# NOR_FLASH.net
KiCad netlist of a schematic drawn in Altium Designer
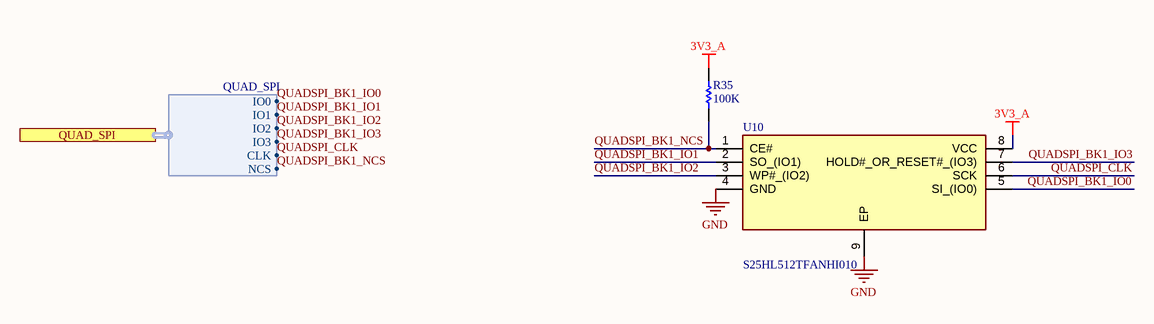
[diagram p0: NOR_FLASH.SchDoc]

(export (version "E")
  (design (tool "Eeschema 10.0.6"))
  (components
    (comp (ref "R35")
      (value "100K")
      (footprint "RESC1608X55X30ML20T10")
      (fields (field (name "PART NUMBER") "RK73B1JTTD104J") (field (name "MANUFACTURER") "KOA Speer"))
      (libsource (lib "Altium Content Vault") (part "RES"))
    )
    (comp (ref "U10")
      (value "S25HL512TFANHI010")
      (footprint "SamacSys:SON127P800X600X80-9N-D")
      (description "Integrated Circuit")
      (fields (field (name "MOUSER PART NUMBER") "727-S25HL512TFANHI01"))
      (libsource (lib "*") (part "S25HL512TFANHI010"))
    )
  )
  (nets
    (net (code "2") (name "/QUADSPI_BK1_IO0") (class "Default")
      (node (ref "U10") (pin "5") (pinfunction "SI_(IO0)_5") (pintype "passive"))
    )
    (net (code "3") (name "/QUADSPI_BK1_IO1") (class "Default")
      (node (ref "U10") (pin "2") (pinfunction "SO_(IO1)_2") (pintype "passive"))
    )
    (net (code "4") (name "/QUADSPI_BK1_IO2") (class "Default")
      (node (ref "U10") (pin "3") (pinfunction "WP#_(IO2)_3") (pintype "passive"))
    )
    (net (code "5") (name "/QUADSPI_BK1_IO3") (class "Default")
      (node (ref "U10") (pin "7") (pinfunction "HOLD#_OR_RESET#_(IO3)_7") (pintype "passive"))
    )
    (net (code "6") (name "/QUADSPI_BK1_NCS") (class "Default")
      (node (ref "R35") (pin "1") (pinfunction "1_1") (pintype "passive"))
      (node (ref "U10") (pin "1") (pinfunction "CE#_1") (pintype "passive"))
    )
    (net (code "7") (name "/QUADSPI_CLK") (class "Default")
      (node (ref "U10") (pin "6") (pinfunction "SCK_6") (pintype "passive"))
    )
    (net (code "9") (name "3V3_A") (class "Default")
      (node (ref "R35") (pin "2") (pinfunction "2_2") (pintype "passive"))
      (node (ref "U10") (pin "8") (pinfunction "VCC_8") (pintype "passive"))
    )
    (net (code "10") (name "GND") (class "Default")
      (node (ref "U10") (pin "4") (pinfunction "GND_4") (pintype "passive"))
      (node (ref "U10") (pin "9") (pinfunction "EP_9") (pintype "passive"))
    )
  )
)
